# Smartwatch.net
KiCad netlist of a schematic drawn in Altium Designer
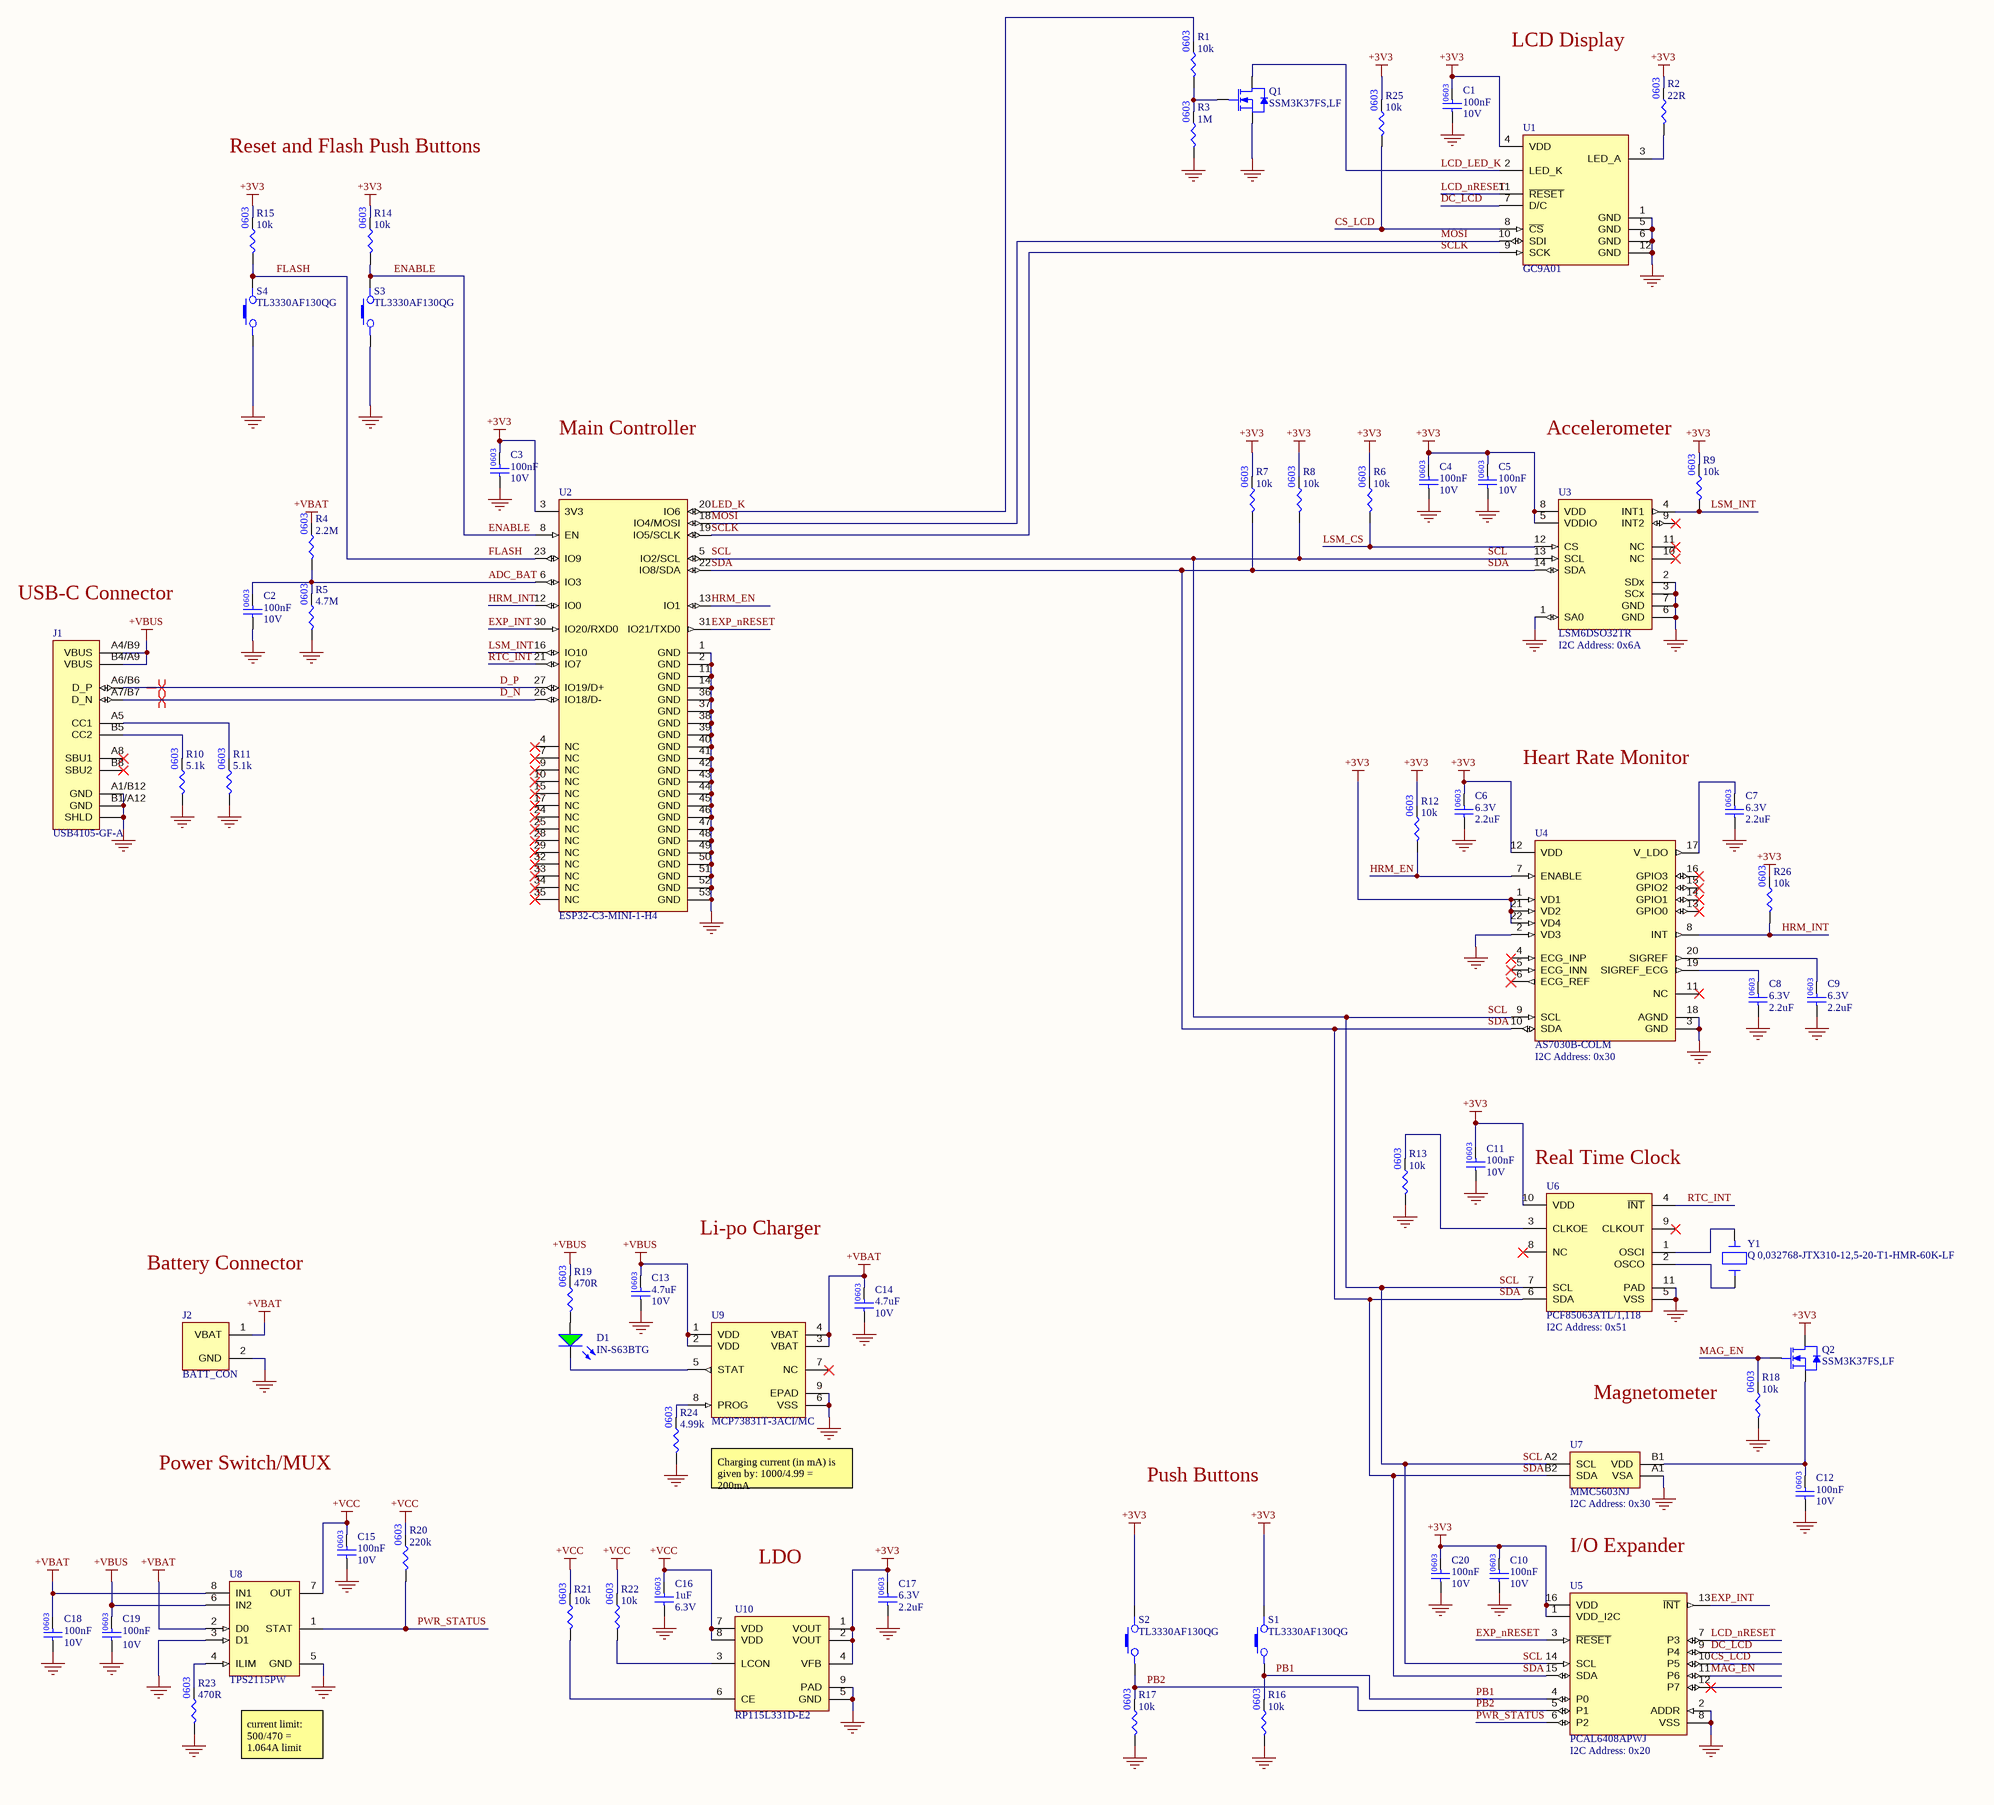
[diagram p0: Smartwatch.SchDoc]

(export (version "E")
  (design (tool "Eeschema 10.0.6"))
  (components
    (comp (ref "C1")
      (value "CC0603KRX7R6BB104")
      (footprint "CAP_0603")
      (description "CAP CER 0.1UF 10V X7R 0603")
      (fields
        (field (name "MANUFACTURER") "Yageo")
        (field (name "TOLERANCE") "10%")
        (field (name "CAPACITANCE") "100nF")
        (field (name "VOLTAGE RATING") "10V")
      )
      (libsource (lib "Smartwatch_Lib") (part "CC0603KRX7R6BB104"))
    )
    (comp (ref "C2")
      (value "CC0603KRX7R6BB104")
      (footprint "CAP_0603")
      (description "CAP CER 0.1UF 10V X7R 0603")
      (fields
        (field (name "MANUFACTURER") "Yageo")
        (field (name "TOLERANCE") "10%")
        (field (name "CAPACITANCE") "100nF")
        (field (name "VOLTAGE RATING") "10V")
      )
      (libsource (lib "Smartwatch_Lib") (part "CC0603KRX7R6BB104"))
    )
    (comp (ref "C3")
      (value "CC0603KRX7R6BB104")
      (footprint "CAP_0603")
      (description "CAP CER 0.1UF 10V X7R 0603")
      (fields
        (field (name "MANUFACTURER") "Yageo")
        (field (name "TOLERANCE") "10%")
        (field (name "CAPACITANCE") "100nF")
        (field (name "VOLTAGE RATING") "10V")
      )
      (libsource (lib "Smartwatch_Lib") (part "CC0603KRX7R6BB104"))
    )
    (comp (ref "C4")
      (value "CC0603KRX7R6BB104")
      (footprint "CAP_0603")
      (description "CAP CER 0.1UF 10V X7R 0603")
      (fields
        (field (name "MANUFACTURER") "Yageo")
        (field (name "TOLERANCE") "10%")
        (field (name "CAPACITANCE") "100nF")
        (field (name "VOLTAGE RATING") "10V")
      )
      (libsource (lib "Smartwatch_Lib") (part "CC0603KRX7R6BB104"))
    )
    (comp (ref "C5")
      (value "CC0603KRX7R6BB104")
      (footprint "CAP_0603")
      (description "CAP CER 0.1UF 10V X7R 0603")
      (fields
        (field (name "MANUFACTURER") "Yageo")
        (field (name "TOLERANCE") "10%")
        (field (name "CAPACITANCE") "100nF")
        (field (name "VOLTAGE RATING") "10V")
      )
      (libsource (lib "Smartwatch_Lib") (part "CC0603KRX7R6BB104"))
    )
    (comp (ref "C6")
      (value "CL10A225KQ8NNNC")
      (footprint "CAP_0603")
      (description "CAP CER 2.2UF 6.3V X5R 0603")
      (fields
        (field (name "MANUFACTURER") "Samsung")
        (field (name "TOLERANCE") "10%")
        (field (name "VOLTAGE RATING") "6.3V")
        (field (name "CAPACITANCE") "2.2uF")
      )
      (libsource (lib "Smartwatch_Lib") (part "CL10A225KQ8NNNC"))
    )
    (comp (ref "C7")
      (value "CL10A225KQ8NNNC")
      (footprint "CAP_0603")
      (description "CAP CER 2.2UF 6.3V X5R 0603")
      (fields
        (field (name "MANUFACTURER") "Samsung")
        (field (name "TOLERANCE") "10%")
        (field (name "VOLTAGE RATING") "6.3V")
        (field (name "CAPACITANCE") "2.2uF")
      )
      (libsource (lib "Smartwatch_Lib") (part "CL10A225KQ8NNNC"))
    )
    (comp (ref "C8")
      (value "CL10A225KQ8NNNC")
      (footprint "CAP_0603")
      (description "CAP CER 2.2UF 6.3V X5R 0603")
      (fields
        (field (name "MANUFACTURER") "Samsung")
        (field (name "TOLERANCE") "10%")
        (field (name "VOLTAGE RATING") "6.3V")
        (field (name "CAPACITANCE") "2.2uF")
      )
      (libsource (lib "Smartwatch_Lib") (part "CL10A225KQ8NNNC"))
    )
    (comp (ref "C9")
      (value "CL10A225KQ8NNNC")
      (footprint "CAP_0603")
      (description "CAP CER 2.2UF 6.3V X5R 0603")
      (fields
        (field (name "MANUFACTURER") "Samsung")
        (field (name "TOLERANCE") "10%")
        (field (name "VOLTAGE RATING") "6.3V")
        (field (name "CAPACITANCE") "2.2uF")
      )
      (libsource (lib "Smartwatch_Lib") (part "CL10A225KQ8NNNC"))
    )
    (comp (ref "C10")
      (value "CC0603KRX7R6BB104")
      (footprint "CAP_0603")
      (description "CAP CER 0.1UF 10V X7R 0603")
      (fields
        (field (name "MANUFACTURER") "Yageo")
        (field (name "TOLERANCE") "10%")
        (field (name "CAPACITANCE") "100nF")
        (field (name "VOLTAGE RATING") "10V")
      )
      (libsource (lib "Smartwatch_Lib") (part "CC0603KRX7R6BB104"))
    )
    (comp (ref "C11")
      (value "CC0603KRX7R6BB104")
      (footprint "CAP_0603")
      (description "CAP CER 0.1UF 10V X7R 0603")
      (fields
        (field (name "MANUFACTURER") "Yageo")
        (field (name "TOLERANCE") "10%")
        (field (name "CAPACITANCE") "100nF")
        (field (name "VOLTAGE RATING") "10V")
      )
      (libsource (lib "Smartwatch_Lib") (part "CC0603KRX7R6BB104"))
    )
    (comp (ref "C12")
      (value "CC0603KRX7R6BB104")
      (footprint "CAP_0603")
      (description "CAP CER 0.1UF 10V X7R 0603")
      (fields
        (field (name "MANUFACTURER") "Yageo")
        (field (name "TOLERANCE") "10%")
        (field (name "CAPACITANCE") "100nF")
        (field (name "VOLTAGE RATING") "10V")
      )
      (libsource (lib "Smartwatch_Lib") (part "CC0603KRX7R6BB104"))
    )
    (comp (ref "C13")
      (value "CL10A475KP8NNNC")
      (footprint "CAP_0603")
      (description "CAP CER 4.7UF 10V X5R 0603")
      (fields
        (field (name "MANUFACTURER") "Samsung")
        (field (name "TOLERANCE") "10%")
        (field (name "CAPACITANCE") "4.7uF")
        (field (name "VOLTAGE RATING") "10V")
      )
      (libsource (lib "Smartwatch_Lib") (part "CL10A475KP8NNNC"))
    )
    (comp (ref "C14")
      (value "CL10A475KP8NNNC")
      (footprint "CAP_0603")
      (description "CAP CER 4.7UF 10V X5R 0603")
      (fields
        (field (name "MANUFACTURER") "Samsung")
        (field (name "TOLERANCE") "10%")
        (field (name "CAPACITANCE") "4.7uF")
        (field (name "VOLTAGE RATING") "10V")
      )
      (libsource (lib "Smartwatch_Lib") (part "CL10A475KP8NNNC"))
    )
    (comp (ref "C15")
      (value "CC0603KRX7R6BB104")
      (footprint "CAP_0603")
      (description "CAP CER 0.1UF 10V X7R 0603")
      (fields
        (field (name "MANUFACTURER") "Yageo")
        (field (name "TOLERANCE") "10%")
        (field (name "CAPACITANCE") "100nF")
        (field (name "VOLTAGE RATING") "10V")
      )
      (libsource (lib "Smartwatch_Lib") (part "CC0603KRX7R6BB104"))
    )
    (comp (ref "C16")
      (value "CL10A105KQ8NNNC")
      (footprint "CAP_0603")
      (description "CAP CER 1UF 6.3V X5R 0603")
      (fields
        (field (name "MANUFACTURER") "Samsung")
        (field (name "TOLERANCE") "10%")
        (field (name "CAPACITANCE") "1uF")
        (field (name "VOLTAGE RATING (DC)") "6.3V")
      )
      (libsource (lib "Smartwatch_Lib") (part "CL10A105KQ8NNNC"))
    )
    (comp (ref "C17")
      (value "CL10A225KQ8NNNC")
      (footprint "CAP_0603")
      (description "CAP CER 2.2UF 6.3V X5R 0603")
      (fields
        (field (name "MANUFACTURER") "Samsung")
        (field (name "TOLERANCE") "10%")
        (field (name "VOLTAGE RATING") "6.3V")
        (field (name "CAPACITANCE") "2.2uF")
      )
      (libsource (lib "Smartwatch_Lib") (part "CL10A225KQ8NNNC"))
    )
    (comp (ref "C18")
      (value "CC0603KRX7R6BB104")
      (footprint "CAP_0603")
      (description "CAP CER 0.1UF 10V X7R 0603")
      (fields
        (field (name "MANUFACTURER") "Yageo")
        (field (name "TOLERANCE") "10%")
        (field (name "CAPACITANCE") "100nF")
        (field (name "VOLTAGE RATING") "10V")
      )
      (libsource (lib "Smartwatch_Lib") (part "CC0603KRX7R6BB104"))
    )
    (comp (ref "C19")
      (value "CC0603KRX7R6BB104")
      (footprint "CAP_0603")
      (description "CAP CER 0.1UF 10V X7R 0603")
      (fields
        (field (name "MANUFACTURER") "Yageo")
        (field (name "TOLERANCE") "10%")
        (field (name "CAPACITANCE") "100nF")
        (field (name "VOLTAGE RATING") "10V")
      )
      (libsource (lib "Smartwatch_Lib") (part "CC0603KRX7R6BB104"))
    )
    (comp (ref "C20")
      (value "CC0603KRX7R6BB104")
      (footprint "CAP_0603")
      (description "CAP CER 0.1UF 10V X7R 0603")
      (fields
        (field (name "MANUFACTURER") "Yageo")
        (field (name "TOLERANCE") "10%")
        (field (name "CAPACITANCE") "100nF")
        (field (name "VOLTAGE RATING") "10V")
      )
      (libsource (lib "Smartwatch_Lib") (part "CC0603KRX7R6BB104"))
    )
    (comp (ref "D1")
      (value "IN-S63BTG")
      (footprint "LED_0603")
      (description "LED Uni-Color Green 530nm 2-Pin Chip 0603(1608Metric) T/R")
      (fields (field (name "MANUFACTURER") "Inolux"))
      (libsource (lib "Smartwatch_Lib") (part "IN-S63BTG"))
    )
    (comp (ref "J1")
      (value "USB4105-GF-A")
      (footprint "USB4105-GF-A")
      (description "Conn USB 2.0 Type C RCP 24 POS 0.3mm/0.5mm Solder RA SMD 24 Terminal 1 Port T/R")
      (fields (field (name "MANUFACTURER") "Global Connector Technology"))
      (libsource (lib "Smartwatch_Lib") (part "USB4105-GF-A"))
    )
    (comp (ref "J2")
      (value "BATT_CON")
      (footprint "BATT_CON")
      (description "Pads for Battery Connection")
      (libsource (lib "Smartwatch_Lib") (part "BATT_CON"))
    )
    (comp (ref "Q1")
      (value "SSM3K37FS,LF")
      (footprint "SSM3K37FS,LF")
      (description "MOSFET NCH 20V 200MA SSM")
      (fields
        (field (name "MANUFACTURER") "Toshiba")
        (field (name "MANUFACTURER PART NUMBER") "SSM3K37FS,LF")
      )
      (libsource (lib "Smartwatch_Lib") (part "SSM3K37FS,LF"))
    )
    (comp (ref "Q2")
      (value "SSM3K37FS,LF")
      (footprint "SSM3K37FS,LF")
      (description "MOSFET NCH 20V 200MA SSM")
      (fields
        (field (name "MANUFACTURER") "Toshiba")
        (field (name "MANUFACTURER PART NUMBER") "SSM3K37FS,LF")
      )
      (libsource (lib "Smartwatch_Lib") (part "SSM3K37FS,LF"))
    )
    (comp (ref "R1")
      (value "RNCP0603FTD10K0")
      (footprint "RES_0603")
      (description "Res Thin Film 0603 10K Ohm 1% 1/8W ±100ppm/°C Molded SMD SMD Paper T/R")
      (fields
        (field (name "MANUFACTURER") "Stackpole Electronics")
        (field (name "TOLERANCE") "1%")
        (field (name "RESISTANCE") "10k")
      )
      (libsource (lib "Smartwatch_Lib") (part "RNCP0603FTD10K0"))
    )
    (comp (ref "R2")
      (value "RC0603FR-0722RL")
      (footprint "RES_0603")
      (description "RES 22 OHM 1% 1/10W 0603")
      (fields
        (field (name "MANUFACTURER") "Yageo")
        (field (name "TOLERANCE") "1%")
        (field (name "RESISTANCE") "22R")
      )
      (libsource (lib "Smartwatch_Lib") (part "RC0603FR-0722RL"))
    )
    (comp (ref "R3")
      (value "RC0603FR-071ML")
      (footprint "RES_0603")
      (description "RES 1M OHM 1% 1/10W 0603")
      (fields
        (field (name "MANUFACTURER") "Yageo")
        (field (name "TOLERANCE") "1%")
        (field (name "RESISTANCE") "1M")
      )
      (libsource (lib "Smartwatch_Lib") (part "RC0603FR-071ML"))
    )
    (comp (ref "R4")
      (value "RC0603FR-072M2L")
      (footprint "RES_0603")
      (description "RES SMD 2.2M OHM 1% 1/10W 0603")
      (fields
        (field (name "MANUFACTURER") "Yageo")
        (field (name "TOLERANCE") "1%")
        (field (name "RESISTANCE") "2.2M")
      )
      (libsource (lib "Smartwatch_Lib") (part "RC0603FR-072M2L"))
    )
    (comp (ref "R5")
      (value "RC0603FR-074M7L")
      (footprint "RES_0603")
      (description "RES 4.7M OHM 1% 1/10W 0603")
      (fields
        (field (name "MANUFACTURER") "Yageo")
        (field (name "TOLERANCE") "1%")
        (field (name "RESISTANCE") "4.7M")
      )
      (libsource (lib "Smartwatch_Lib") (part "RC0603FR-074M7L"))
    )
    (comp (ref "R6")
      (value "RNCP0603FTD10K0")
      (footprint "RES_0603")
      (description "Res Thin Film 0603 10K Ohm 1% 1/8W ±100ppm/°C Molded SMD SMD Paper T/R")
      (fields
        (field (name "MANUFACTURER") "Stackpole Electronics")
        (field (name "TOLERANCE") "1%")
        (field (name "RESISTANCE") "10k")
      )
      (libsource (lib "Smartwatch_Lib") (part "RNCP0603FTD10K0"))
    )
    (comp (ref "R7")
      (value "RNCP0603FTD10K0")
      (footprint "RES_0603")
      (description "Res Thin Film 0603 10K Ohm 1% 1/8W ±100ppm/°C Molded SMD SMD Paper T/R")
      (fields
        (field (name "MANUFACTURER") "Stackpole Electronics")
        (field (name "TOLERANCE") "1%")
        (field (name "RESISTANCE") "10k")
      )
      (libsource (lib "Smartwatch_Lib") (part "RNCP0603FTD10K0"))
    )
    (comp (ref "R8")
      (value "RNCP0603FTD10K0")
      (footprint "RES_0603")
      (description "Res Thin Film 0603 10K Ohm 1% 1/8W ±100ppm/°C Molded SMD SMD Paper T/R")
      (fields
        (field (name "MANUFACTURER") "Stackpole Electronics")
        (field (name "TOLERANCE") "1%")
        (field (name "RESISTANCE") "10k")
      )
      (libsource (lib "Smartwatch_Lib") (part "RNCP0603FTD10K0"))
    )
    (comp (ref "R9")
      (value "RNCP0603FTD10K0")
      (footprint "RES_0603")
      (description "Res Thin Film 0603 10K Ohm 1% 1/8W ±100ppm/°C Molded SMD SMD Paper T/R")
      (fields
        (field (name "MANUFACTURER") "Stackpole Electronics")
        (field (name "TOLERANCE") "1%")
        (field (name "RESISTANCE") "10k")
      )
      (libsource (lib "Smartwatch_Lib") (part "RNCP0603FTD10K0"))
    )
    (comp (ref "R10")
      (value "RMCF0603FT5K10")
      (footprint "RES_0603")
      (description "Res Thick Film 0603 5.1K Ohm 1% 0.1W(1/10W) ±100ppm/C Pad SMD Automotive T/R")
      (fields
        (field (name "MANUFACTURER") "Stackpole Electronics")
        (field (name "TOLERANCE") "1%")
        (field (name "RESISTANCE") "5.1k")
      )
      (libsource (lib "Smartwatch_Lib") (part "RMCF0603FT5K10"))
    )
    (comp (ref "R11")
      (value "RMCF0603FT5K10")
      (footprint "RES_0603")
      (description "Res Thick Film 0603 5.1K Ohm 1% 0.1W(1/10W) ±100ppm/C Pad SMD Automotive T/R")
      (fields
        (field (name "MANUFACTURER") "Stackpole Electronics")
        (field (name "TOLERANCE") "1%")
        (field (name "RESISTANCE") "5.1k")
      )
      (libsource (lib "Smartwatch_Lib") (part "RMCF0603FT5K10"))
    )
    (comp (ref "R12")
      (value "RNCP0603FTD10K0")
      (footprint "RES_0603")
      (description "Res Thin Film 0603 10K Ohm 1% 1/8W ±100ppm/°C Molded SMD SMD Paper T/R")
      (fields
        (field (name "MANUFACTURER") "Stackpole Electronics")
        (field (name "TOLERANCE") "1%")
        (field (name "RESISTANCE") "10k")
      )
      (libsource (lib "Smartwatch_Lib") (part "RNCP0603FTD10K0"))
    )
    (comp (ref "R13")
      (value "RNCP0603FTD10K0")
      (footprint "RES_0603")
      (description "Res Thin Film 0603 10K Ohm 1% 1/8W ±100ppm/°C Molded SMD SMD Paper T/R")
      (fields
        (field (name "MANUFACTURER") "Stackpole Electronics")
        (field (name "TOLERANCE") "1%")
        (field (name "RESISTANCE") "10k")
      )
      (libsource (lib "Smartwatch_Lib") (part "RNCP0603FTD10K0"))
    )
    (comp (ref "R14")
      (value "RNCP0603FTD10K0")
      (footprint "RES_0603")
      (description "Res Thin Film 0603 10K Ohm 1% 1/8W ±100ppm/°C Molded SMD SMD Paper T/R")
      (fields
        (field (name "MANUFACTURER") "Stackpole Electronics")
        (field (name "TOLERANCE") "1%")
        (field (name "RESISTANCE") "10k")
      )
      (libsource (lib "Smartwatch_Lib") (part "RNCP0603FTD10K0"))
    )
    (comp (ref "R15")
      (value "RNCP0603FTD10K0")
      (footprint "RES_0603")
      (description "Res Thin Film 0603 10K Ohm 1% 1/8W ±100ppm/°C Molded SMD SMD Paper T/R")
      (fields
        (field (name "MANUFACTURER") "Stackpole Electronics")
        (field (name "TOLERANCE") "1%")
        (field (name "RESISTANCE") "10k")
      )
      (libsource (lib "Smartwatch_Lib") (part "RNCP0603FTD10K0"))
    )
    (comp (ref "R16")
      (value "RNCP0603FTD10K0")
      (footprint "RES_0603")
      (description "Res Thin Film 0603 10K Ohm 1% 1/8W ±100ppm/°C Molded SMD SMD Paper T/R")
      (fields
        (field (name "MANUFACTURER") "Stackpole Electronics")
        (field (name "TOLERANCE") "1%")
        (field (name "RESISTANCE") "10k")
      )
      (libsource (lib "Smartwatch_Lib") (part "RNCP0603FTD10K0"))
    )
    (comp (ref "R17")
      (value "RNCP0603FTD10K0")
      (footprint "RES_0603")
      (description "Res Thin Film 0603 10K Ohm 1% 1/8W ±100ppm/°C Molded SMD SMD Paper T/R")
      (fields
        (field (name "MANUFACTURER") "Stackpole Electronics")
        (field (name "TOLERANCE") "1%")
        (field (name "RESISTANCE") "10k")
      )
      (libsource (lib "Smartwatch_Lib") (part "RNCP0603FTD10K0"))
    )
    (comp (ref "R18")
      (value "RNCP0603FTD10K0")
      (footprint "RES_0603")
      (description "Res Thin Film 0603 10K Ohm 1% 1/8W ±100ppm/°C Molded SMD SMD Paper T/R")
      (fields
        (field (name "MANUFACTURER") "Stackpole Electronics")
        (field (name "TOLERANCE") "1%")
        (field (name "RESISTANCE") "10k")
      )
      (libsource (lib "Smartwatch_Lib") (part "RNCP0603FTD10K0"))
    )
    (comp (ref "R19")
      (value "RC0603FR-07470RL")
      (footprint "RES_0603")
      (description "RES 470 OHM 1% 1/10W 0603")
      (fields
        (field (name "MANUFACTURER") "Yageo")
        (field (name "TOLERANCE") "1%")
        (field (name "RESISTANCE") "470R")
      )
      (libsource (lib "Smartwatch_Lib") (part "RC0603FR-07470RL"))
    )
    (comp (ref "R20")
      (value "RMCF0603FT220K")
      (footprint "RES_0603")
      (description "Res Thick Film 0603 220K Ohm 1% 0.1W(1/10W) ±100ppm/C Pad SMD Automotive T/R")
      (fields
        (field (name "MANUFACTURER") "Stackpole Electronics")
        (field (name "TOLERANCE") "1%")
        (field (name "RESISTANCE") "220k")
      )
      (libsource (lib "Smartwatch_Lib") (part "RMCF0603FT220K"))
    )
    (comp (ref "R21")
      (value "RNCP0603FTD10K0")
      (footprint "RES_0603")
      (description "Res Thin Film 0603 10K Ohm 1% 1/8W ±100ppm/°C Molded SMD SMD Paper T/R")
      (fields
        (field (name "MANUFACTURER") "Stackpole Electronics")
        (field (name "TOLERANCE") "1%")
        (field (name "RESISTANCE") "10k")
      )
      (libsource (lib "Smartwatch_Lib") (part "RNCP0603FTD10K0"))
    )
    (comp (ref "R22")
      (value "RNCP0603FTD10K0")
      (footprint "RES_0603")
      (description "Res Thin Film 0603 10K Ohm 1% 1/8W ±100ppm/°C Molded SMD SMD Paper T/R")
      (fields
        (field (name "MANUFACTURER") "Stackpole Electronics")
        (field (name "TOLERANCE") "1%")
        (field (name "RESISTANCE") "10k")
      )
      (libsource (lib "Smartwatch_Lib") (part "RNCP0603FTD10K0"))
    )
    (comp (ref "R23")
      (value "RC0603FR-07470RL")
      (footprint "RES_0603")
      (description "RES 470 OHM 1% 1/10W 0603")
      (fields
        (field (name "MANUFACTURER") "Yageo")
        (field (name "TOLERANCE") "1%")
        (field (name "RESISTANCE") "470R")
      )
      (libsource (lib "Smartwatch_Lib") (part "RC0603FR-07470RL"))
    )
    (comp (ref "R24")
      (value "RC0603FR-074K99L")
      (footprint "RES_0603")
      (description "RES 4.99K OHM 1% 1/10W 0603")
      (fields
        (field (name "MANUFACTURER") "Yageo")
        (field (name "TOLERANCE") "1%")
        (field (name "RESISTANCE") "4.99k")
      )
      (libsource (lib "Smartwatch_Lib") (part "RC0603FR-074K99L"))
    )
    (comp (ref "R25")
      (value "RNCP0603FTD10K0")
      (footprint "RES_0603")
      (description "Res Thin Film 0603 10K Ohm 1% 1/8W ±100ppm/°C Molded SMD SMD Paper T/R")
      (fields
        (field (name "MANUFACTURER") "Stackpole Electronics")
        (field (name "TOLERANCE") "1%")
        (field (name "RESISTANCE") "10k")
      )
      (libsource (lib "Smartwatch_Lib") (part "RNCP0603FTD10K0"))
    )
    (comp (ref "R26")
      (value "RNCP0603FTD10K0")
      (footprint "RES_0603")
      (description "Res Thin Film 0603 10K Ohm 1% 1/8W ±100ppm/°C Molded SMD SMD Paper T/R")
      (fields
        (field (name "MANUFACTURER") "Stackpole Electronics")
        (field (name "TOLERANCE") "1%")
        (field (name "RESISTANCE") "10k")
      )
      (libsource (lib "Smartwatch_Lib") (part "RNCP0603FTD10K0"))
    )
    (comp (ref "S1")
      (value "TL3330AF130QG")
      (footprint "TL3330AF130QG")
      (description "Switch Tactile N.O. SPST Rectangular Button Gull Wing 0.05A 12VDC 50000Cycles 1.27N SMD T/R")
      (fields
        (field (name "MANUFACTURER") "E-Switch")
        (field (name "MANUFACTURER PART NUMBER") "TL3330AF130QG")
      )
      (libsource (lib "Smartwatch_Lib") (part "TL3330AF130QG"))
    )
    (comp (ref "S2")
      (value "TL3330AF130QG")
      (footprint "TL3330AF130QG")
      (description "Switch Tactile N.O. SPST Rectangular Button Gull Wing 0.05A 12VDC 50000Cycles 1.27N SMD T/R")
      (fields
        (field (name "MANUFACTURER") "E-Switch")
        (field (name "MANUFACTURER PART NUMBER") "TL3330AF130QG")
      )
      (libsource (lib "Smartwatch_Lib") (part "TL3330AF130QG"))
    )
    (comp (ref "S3")
      (value "TL3330AF130QG")
      (footprint "TL3330AF130QG")
      (description "Switch Tactile N.O. SPST Rectangular Button Gull Wing 0.05A 12VDC 50000Cycles 1.27N SMD T/R")
      (fields
        (field (name "MANUFACTURER") "E-Switch")
        (field (name "MANUFACTURER PART NUMBER") "TL3330AF130QG")
      )
      (libsource (lib "Smartwatch_Lib") (part "TL3330AF130QG"))
    )
    (comp (ref "S4")
      (value "TL3330AF130QG")
      (footprint "TL3330AF130QG")
      (description "Switch Tactile N.O. SPST Rectangular Button Gull Wing 0.05A 12VDC 50000Cycles 1.27N SMD T/R")
      (fields
        (field (name "MANUFACTURER") "E-Switch")
        (field (name "MANUFACTURER PART NUMBER") "TL3330AF130QG")
      )
      (libsource (lib "Smartwatch_Lib") (part "TL3330AF130QG"))
    )
    (comp (ref "U1")
      (value "GC9A01")
      (footprint "GC9A01")
      (description "GC9A01 LCD Display")
      (libsource (lib "Smartwatch_Lib") (part "GC9A01"))
    )
    (comp (ref "U2")
      (value "ESP32-C3-MINI-1-H4")
      (footprint "ESP32-C3-MINI-1-H4")
      (description "SMD Module, ESP32-C3FH4, Pcb Ant")
      (fields (field (name "MANUFACTURER") "Espressif Systems"))
      (libsource (lib "Smartwatch_Lib") (part "ESP32-C3-MINI-1-H4"))
    )
    (comp (ref "U3")
      (value "LSM6DSO32TR")
      (footprint "LSM6DSO32")
      (description "Accelerometer and 3D Gyroscope 3D Always-On 1.71V to 3.6V 0.55mA 14-Pin LGA T/R")
      (fields (field (name "MANUFACTURER") "STMicroelectronics"))
      (libsource (lib "Smartwatch_Lib") (part "LSM6DSO32TR"))
    )
    (comp (ref "U4")
      (value "AS7030B-COLM")
      (footprint "AS7030B-COLM")
      (description "AS703x Series 5.5 V Medical or Consumer Grade Vital Sign Sensor Module - OLGA-22")
      (fields (field (name "MANUFACTURER") "ams"))
      (libsource (lib "Smartwatch_Lib") (part "AS7030B-COLM"))
    )
    (comp (ref "U5")
      (value "PCAL6408APWJ")
      (footprint "PCAL6408APWJ")
      (description "NXP - PCAL6408APWJ - I/O-Erweiterung, 8bit, 400 kHz, I2C, 1.65 V, 5.5 V, TSSOP")
      (fields
        (field (name "MANUFACTURER") "NXP Semiconductors")
        (field (name "MANUFACTURER PART NUMBER") "PCAL6408APWJ")
      )
      (libsource (lib "Smartwatch_Lib") (part "PCAL6408APWJ"))
    )
    (comp (ref "U6")
      (value "PCF85063ATL/1,118")
      (footprint "PCF85063ATL/1,118")
      (description "IC RTC CLK/CALENDAR I2C 10-SON")
      (fields (field (name "MANUFACTURER") "NXP Semiconductors"))
      (libsource (lib "Smartwatch_Lib") (part "PCF85063ATL/1,118"))
    )
    (comp (ref "U7")
      (value "MMC5603NJ")
      (footprint "MMC5603NJ")
      (description "3-AXIS Amr Magnetic Sensor")
      (fields (field (name "MANUFACTURER") "Memsic") (field (name "MANUFACTURER PART NUMBER") "MMC5603NJ"))
      (libsource (lib "Smartwatch_Lib") (part "MMC5603NJ"))
    )
    (comp (ref "U8")
      (value "TPS2115PW")
      (footprint "TPS2115PW")
      (description "Pwr Mux Autoswitch 1.5V to 5.5V 1.25A 8-Pin TSSOP Tube")
      (fields (field (name "MANUFACTURER") "Texas Instruments"))
      (libsource (lib "Smartwatch_Lib") (part "TPS2115PW"))
    )
    (comp (ref "U9")
      (value "MCP73831T-3ACI/MC")
      (footprint "MCP73831T-3ACI/MC")
      (description "Battery Management - Advanced Lithium-Ion/-Polymer Charge mgnt contr")
      (fields (field (name "MANUFACTURER") "Microchip"))
      (libsource (lib "Smartwatch_Lib") (part "MCP73831T-3ACI/MC"))
    )
    (comp (ref "U10")
      (value "RP115L331D-E2")
      (footprint "RP115L331D-E2")
      (description "LDO Regulator Pos 3.3V 0.5A/1A 8-Pin DFN EP T/R")
      (fields (field (name "MANUFACTURER") "Ricoh"))
      (libsource (lib "Smartwatch_Lib") (part "RP115L331D-E2"))
    )
    (comp (ref "Y1")
      (value "Q 0,032768-JTX310-12,5-20-T1-HMR-60K-LF")
      (footprint "Q 0,032768-JTX310-12,5-20-T1-HMR-60K-LF")
      (description "Crystal 32.7680KHZ 12.5PF SMD")
      (fields
        (field (name "MANUFACTURER") "Jauch")
        (field (name "MANUFACTURER PART NUMBER") "Q 0,032768-JTX310-12,5-20-T1-HMR-60K-LF")
      )
      (libsource (lib "Smartwatch_Lib") (part "Q 0,032768-JTX310-12,5-20-T1-HMR-60K-LF"))
    )
  )
  (nets
    (net (code "1") (name "+3V3") (class "Default")
      (node (ref "C1") (pin "2") (pinfunction "2_2") (pintype "passive"))
      (node (ref "C10") (pin "2") (pinfunction "2_2") (pintype "passive"))
      (node (ref "C11") (pin "2") (pinfunction "2_2") (pintype "passive"))
      (node (ref "C17") (pin "2") (pinfunction "2_2") (pintype "passive"))
      (node (ref "C20") (pin "2") (pinfunction "2_2") (pintype "passive"))
      (node (ref "C3") (pin "2") (pinfunction "2_2") (pintype "passive"))
      (node (ref "C4") (pin "2") (pinfunction "2_2") (pintype "passive"))
      (node (ref "C5") (pin "2") (pinfunction "2_2") (pintype "passive"))
      (node (ref "C6") (pin "2") (pinfunction "2_2") (pintype "passive"))
      (node (ref "Q2") (pin "1") (pinfunction "Drain_1") (pintype "passive"))
      (node (ref "R12") (pin "2") (pinfunction "2_2") (pintype "passive"))
      (node (ref "R14") (pin "2") (pinfunction "2_2") (pintype "passive"))
      (node (ref "R15") (pin "2") (pinfunction "2_2") (pintype "passive"))
      (node (ref "R2") (pin "2") (pinfunction "2_2") (pintype "passive"))
      (node (ref "R25") (pin "2") (pinfunction "2_2") (pintype "passive"))
      (node (ref "R26") (pin "2") (pinfunction "2_2") (pintype "passive"))
      (node (ref "R6") (pin "2") (pinfunction "2_2") (pintype "passive"))
      (node (ref "R7") (pin "2") (pinfunction "2_2") (pintype "passive"))
      (node (ref "R8") (pin "2") (pinfunction "2_2") (pintype "passive"))
      (node (ref "R9") (pin "2") (pinfunction "2_2") (pintype "passive"))
      (node (ref "S1") (pin "1") (pintype "passive"))
      (node (ref "S2") (pin "1") (pintype "passive"))
      (node (ref "U1") (pin "4") (pinfunction "VDD_4") (pintype "passive"))
      (node (ref "U10") (pin "1") (pinfunction "VOUT_1") (pintype "passive"))
      (node (ref "U10") (pin "2") (pinfunction "VOUT_2") (pintype "passive"))
      (node (ref "U10") (pin "4") (pinfunction "VFB_4") (pintype "passive"))
      (node (ref "U2") (pin "3") (pinfunction "3V3_3") (pintype "power_in"))
      (node (ref "U3") (pin "5") (pinfunction "VDDIO_5") (pintype "power_in"))
      (node (ref "U3") (pin "8") (pinfunction "VDD_8") (pintype "power_in"))
      (node (ref "U4") (pin "1") (pinfunction "VD1_1") (pintype "input"))
      (node (ref "U4") (pin "12") (pinfunction "VDD_12") (pintype "power_in"))
      (node (ref "U4") (pin "21") (pinfunction "VD2_21") (pintype "input"))
      (node (ref "U4") (pin "22") (pinfunction "VD4_22") (pintype "input"))
      (node (ref "U5") (pin "1") (pinfunction "VDD_I2C_1") (pintype "power_in"))
      (node (ref "U5") (pin "16") (pinfunction "VDD_16") (pintype "power_in"))
      (node (ref "U6") (pin "10") (pinfunction "VDD_10") (pintype "passive"))
    )
    (net (code "2") (name "+VBAT") (class "Default")
      (node (ref "C14") (pin "2") (pinfunction "2_2") (pintype "passive"))
      (node (ref "C18") (pin "2") (pinfunction "2_2") (pintype "passive"))
      (node (ref "J2") (pin "1") (pinfunction "VBAT_1") (pintype "passive"))
      (node (ref "R4") (pin "2") (pinfunction "2_2") (pintype "passive"))
      (node (ref "U8") (pin "2") (pinfunction "D0_2") (pintype "input"))
      (node (ref "U8") (pin "8") (pinfunction "IN1_8") (pintype "power_in"))
      (node (ref "U9") (pin "3") (pinfunction "VBAT_3") (pintype "passive"))
      (node (ref "U9") (pin "4") (pinfunction "VBAT_4") (pintype "passive"))
    )
    (net (code "3") (name "+VBUS") (class "Default")
      (node (ref "C13") (pin "2") (pinfunction "2_2") (pintype "passive"))
      (node (ref "C19") (pin "2") (pinfunction "2_2") (pintype "passive"))
      (node (ref "J1") (pin "A4/B9") (pinfunction "VBUS_A4/B9") (pintype "power_in"))
      (node (ref "J1") (pin "B4/A9") (pinfunction "VBUS_B4/A9") (pintype "power_in"))
      (node (ref "R19") (pin "2") (pinfunction "2_2") (pintype "passive"))
      (node (ref "U8") (pin "6") (pinfunction "IN2_6") (pintype "power_in"))
      (node (ref "U9") (pin "1") (pinfunction "VDD_1") (pintype "passive"))
      (node (ref "U9") (pin "2") (pinfunction "VDD_2") (pintype "passive"))
    )
    (net (code "4") (name "+VCC") (class "Default")
      (node (ref "C15") (pin "2") (pinfunction "2_2") (pintype "passive"))
      (node (ref "C16") (pin "2") (pinfunction "2_2") (pintype "passive"))
      (node (ref "R20") (pin "2") (pinfunction "2_2") (pintype "passive"))
      (node (ref "R21") (pin "2") (pinfunction "2_2") (pintype "passive"))
      (node (ref "R22") (pin "2") (pinfunction "2_2") (pintype "passive"))
      (node (ref "U10") (pin "7") (pinfunction "VDD_7") (pintype "passive"))
      (node (ref "U10") (pin "8") (pinfunction "VDD_8") (pintype "passive"))
      (node (ref "U8") (pin "7") (pinfunction "OUT_7") (pintype "power_in"))
    )
    (net (code "5") (name "/ADC_BAT") (class "Default")
      (node (ref "C2") (pin "2") (pinfunction "2_2") (pintype "passive"))
      (node (ref "R4") (pin "1") (pinfunction "1_1") (pintype "passive"))
      (node (ref "R5") (pin "2") (pinfunction "2_2") (pintype "passive"))
      (node (ref "U2") (pin "6") (pinfunction "IO3_6") (pintype "bidirectional"))
    )
    (net (code "6") (name "/CS_LCD") (class "Default")
      (node (ref "R25") (pin "1") (pinfunction "1_1") (pintype "passive"))
      (node (ref "U1") (pin "8") (pinfunction "~{CS}_8") (pintype "input"))
      (node (ref "U5") (pin "10") (pinfunction "P5_10") (pintype "bidirectional"))
    )
    (net (code "7") (name "/DC_LCD") (class "Default")
      (node (ref "U1") (pin "7") (pinfunction "D/C_7") (pintype "passive"))
      (node (ref "U5") (pin "9") (pinfunction "P4_9") (pintype "bidirectional"))
    )
    (net (code "8") (name "/D_N") (class "Default")
      (node (ref "J1") (pin "A7/B7") (pinfunction "D_N_A7/B7") (pintype "bidirectional"))
      (node (ref "U2") (pin "26") (pinfunction "IO18/D-_26") (pintype "bidirectional"))
    )
    (net (code "9") (name "/D_P") (class "Default")
      (node (ref "J1") (pin "A6/B6") (pinfunction "D_P_A6/B6") (pintype "bidirectional"))
      (node (ref "U2") (pin "27") (pinfunction "IO19/D+_27") (pintype "bidirectional"))
    )
    (net (code "10") (name "/ENABLE") (class "Default")
      (node (ref "R14") (pin "1") (pinfunction "1_1") (pintype "passive"))
      (node (ref "S3") (pin "1") (pintype "passive"))
      (node (ref "U2") (pin "8") (pinfunction "EN_8") (pintype "input"))
    )
    (net (code "11") (name "/EXP_INT") (class "Default")
      (node (ref "U2") (pin "30") (pinfunction "IO20/RXD0_30") (pintype "input"))
      (node (ref "U5") (pin "13") (pinfunction "~{INT}_13") (pintype "output"))
    )
    (net (code "12") (name "/EXP_nRESET") (class "Default")
      (node (ref "U2") (pin "31") (pinfunction "IO21/TXD0_31") (pintype "output"))
      (node (ref "U5") (pin "3") (pinfunction "~{RESET}_3") (pintype "input"))
    )
    (net (code "13") (name "/FLASH") (class "Default")
      (node (ref "R15") (pin "1") (pinfunction "1_1") (pintype "passive"))
      (node (ref "S4") (pin "1") (pintype "passive"))
      (node (ref "U2") (pin "23") (pinfunction "IO9_23") (pintype "bidirectional"))
    )
    (net (code "14") (name "/HRM_EN") (class "Default")
      (node (ref "R12") (pin "1") (pinfunction "1_1") (pintype "passive"))
      (node (ref "U2") (pin "13") (pinfunction "IO1_13") (pintype "bidirectional"))
      (node (ref "U4") (pin "7") (pinfunction "ENABLE_7") (pintype "input"))
    )
    (net (code "15") (name "/HRM_INT") (class "Default")
      (node (ref "R26") (pin "1") (pinfunction "1_1") (pintype "passive"))
      (node (ref "U2") (pin "12") (pinfunction "IO0_12") (pintype "bidirectional"))
      (node (ref "U4") (pin "8") (pinfunction "INT_8") (pintype "output"))
    )
    (net (code "16") (name "/LCD_LED_K") (class "Default")
      (node (ref "Q1") (pin "1") (pinfunction "Drain_1") (pintype "passive"))
      (node (ref "U1") (pin "2") (pinfunction "LED_K_2") (pintype "passive"))
    )
    (net (code "17") (name "/LCD_nRESET") (class "Default")
      (node (ref "U1") (pin "11") (pinfunction "~{RESET}_11") (pintype "passive"))
      (node (ref "U5") (pin "7") (pinfunction "P3_7") (pintype "bidirectional"))
    )
    (net (code "18") (name "/LED_K") (class "Default")
      (node (ref "R1") (pin "2") (pinfunction "2_2") (pintype "passive"))
      (node (ref "U2") (pin "20") (pinfunction "IO6_20") (pintype "bidirectional"))
    )
    (net (code "19") (name "/LSM_CS") (class "Default")
      (node (ref "R6") (pin "1") (pinfunction "1_1") (pintype "passive"))
      (node (ref "U3") (pin "12") (pinfunction "CS_12") (pintype "input"))
    )
    (net (code "20") (name "/LSM_INT") (class "Default")
      (node (ref "R9") (pin "1") (pinfunction "1_1") (pintype "passive"))
      (node (ref "U2") (pin "16") (pinfunction "IO10_16") (pintype "bidirectional"))
      (node (ref "U3") (pin "4") (pinfunction "INT1_4") (pintype "output"))
    )
    (net (code "21") (name "/MAG_EN") (class "Default")
      (node (ref "Q2") (pin "2") (pinfunction "Gate_2") (pintype "passive"))
      (node (ref "R18") (pin "2") (pinfunction "2_2") (pintype "passive"))
      (node (ref "U5") (pin "11") (pinfunction "P6_11") (pintype "bidirectional"))
    )
    (net (code "22") (name "/MOSI") (class "Default")
      (node (ref "U1") (pin "10") (pinfunction "SDI_10") (pintype "bidirectional"))
      (node (ref "U2") (pin "18") (pinfunction "IO4/MOSI_18") (pintype "bidirectional"))
    )
    (net (code "23") (name "/PB1") (class "Default")
      (node (ref "R16") (pin "2") (pinfunction "2_2") (pintype "passive"))
      (node (ref "S1") (pin "2") (pintype "passive"))
      (node (ref "U5") (pin "4") (pinfunction "P0_4") (pintype "bidirectional"))
    )
    (net (code "24") (name "/PB2") (class "Default")
      (node (ref "R17") (pin "2") (pinfunction "2_2") (pintype "passive"))
      (node (ref "S2") (pin "2") (pintype "passive"))
      (node (ref "U5") (pin "5") (pinfunction "P1_5") (pintype "bidirectional"))
    )
    (net (code "25") (name "/PWR_STATUS") (class "Default")
      (node (ref "R20") (pin "1") (pinfunction "1_1") (pintype "passive"))
      (node (ref "U5") (pin "6") (pinfunction "P2_6") (pintype "bidirectional"))
      (node (ref "U8") (pin "1") (pinfunction "STAT_1") (pintype "tri_state"))
    )
    (net (code "26") (name "/RTC_INT") (class "Default")
      (node (ref "U2") (pin "21") (pinfunction "IO7_21") (pintype "bidirectional"))
      (node (ref "U6") (pin "4") (pinfunction "~{INT}_4") (pintype "passive"))
    )
    (net (code "27") (name "/SCL") (class "Default")
      (node (ref "R8") (pin "1") (pinfunction "1_1") (pintype "passive"))
      (node (ref "U2") (pin "5") (pinfunction "IO2/SCL_5") (pintype "bidirectional"))
      (node (ref "U3") (pin "13") (pinfunction "SCL_13") (pintype "input"))
      (node (ref "U4") (pin "9") (pinfunction "SCL_9") (pintype "input"))
      (node (ref "U5") (pin "14") (pinfunction "SCL_14") (pintype "input"))
      (node (ref "U6") (pin "7") (pinfunction "SCL_7") (pintype "passive"))
      (node (ref "U7") (pin "A2") (pinfunction "SCL_A2") (pintype "passive"))
    )
    (net (code "28") (name "/SCLK") (class "Default")
      (node (ref "U1") (pin "9") (pinfunction "SCK_9") (pintype "input"))
      (node (ref "U2") (pin "19") (pinfunction "IO5/SCLK_19") (pintype "bidirectional"))
    )
    (net (code "29") (name "/SDA") (class "Default")
      (node (ref "R7") (pin "1") (pinfunction "1_1") (pintype "passive"))
      (node (ref "U2") (pin "22") (pinfunction "IO8/SDA_22") (pintype "bidirectional"))
      (node (ref "U3") (pin "14") (pinfunction "SDA_14") (pintype "bidirectional"))
      (node (ref "U4") (pin "10") (pinfunction "SDA_10") (pintype "bidirectional"))
      (node (ref "U5") (pin "15") (pinfunction "SDA_15") (pintype "bidirectional"))
      (node (ref "U6") (pin "6") (pinfunction "SDA_6") (pintype "passive"))
      (node (ref "U7") (pin "B2") (pinfunction "SDA_B2") (pintype "passive"))
    )
    (net (code "30") (name "GND") (class "Default")
      (node (ref "C1") (pin "1") (pinfunction "1_1") (pintype "passive"))
      (node (ref "C10") (pin "1") (pinfunction "1_1") (pintype "passive"))
      (node (ref "C11") (pin "1") (pinfunction "1_1") (pintype "passive"))
      (node (ref "C12") (pin "1") (pinfunction "1_1") (pintype "passive"))
      (node (ref "C13") (pin "1") (pinfunction "1_1") (pintype "passive"))
      (node (ref "C14") (pin "1") (pinfunction "1_1") (pintype "passive"))
      (node (ref "C15") (pin "1") (pinfunction "1_1") (pintype "passive"))
      (node (ref "C16") (pin "1") (pinfunction "1_1") (pintype "passive"))
      (node (ref "C17") (pin "1") (pinfunction "1_1") (pintype "passive"))
      (node (ref "C18") (pin "1") (pinfunction "1_1") (pintype "passive"))
      (node (ref "C19") (pin "1") (pinfunction "1_1") (pintype "passive"))
      (node (ref "C2") (pin "1") (pinfunction "1_1") (pintype "passive"))
      (node (ref "C20") (pin "1") (pinfunction "1_1") (pintype "passive"))
      (node (ref "C3") (pin "1") (pinfunction "1_1") (pintype "passive"))
      (node (ref "C4") (pin "1") (pinfunction "1_1") (pintype "passive"))
      (node (ref "C5") (pin "1") (pinfunction "1_1") (pintype "passive"))
      (node (ref "C6") (pin "1") (pinfunction "1_1") (pintype "passive"))
      (node (ref "C7") (pin "1") (pinfunction "1_1") (pintype "passive"))
      (node (ref "C8") (pin "1") (pinfunction "1_1") (pintype "passive"))
      (node (ref "C9") (pin "1") (pinfunction "1_1") (pintype "passive"))
      (node (ref "J1") (pin "A1/B12") (pinfunction "GND_A1/B12") (pintype "power_in"))
      (node (ref "J1") (pin "B1/A12") (pinfunction "GND_B1/A12") (pintype "power_in"))
      (node (ref "J1") (pin "SHLD") (pinfunction "SHLD_SHLD") (pintype "power_in"))
      (node (ref "J2") (pin "2") (pinfunction "GND_2") (pintype "passive"))
      (node (ref "Q1") (pin "3") (pinfunction "Source_3") (pintype "passive"))
      (node (ref "R10") (pin "1") (pinfunction "1_1") (pintype "passive"))
      (node (ref "R11") (pin "1") (pinfunction "1_1") (pintype "passive"))
      (node (ref "R13") (pin "1") (pinfunction "1_1") (pintype "passive"))
      (node (ref "R16") (pin "1") (pinfunction "1_1") (pintype "passive"))
      (node (ref "R17") (pin "1") (pinfunction "1_1") (pintype "passive"))
      (node (ref "R18") (pin "1") (pinfunction "1_1") (pintype "passive"))
      (node (ref "R23") (pin "1") (pinfunction "1_1") (pintype "passive"))
      (node (ref "R24") (pin "1") (pinfunction "1_1") (pintype "passive"))
      (node (ref "R3") (pin "1") (pinfunction "1_1") (pintype "passive"))
      (node (ref "R5") (pin "1") (pinfunction "1_1") (pintype "passive"))
      (node (ref "S3") (pin "2") (pintype "passive"))
      (node (ref "S4") (pin "2") (pintype "passive"))
      (node (ref "U1") (pin "1") (pinfunction "GND_1") (pintype "passive"))
      (node (ref "U1") (pin "12") (pinfunction "GND_12") (pintype "passive"))
      (node (ref "U1") (pin "5") (pinfunction "GND_5") (pintype "passive"))
      (node (ref "U1") (pin "6") (pinfunction "GND_6") (pintype "passive"))
      (node (ref "U10") (pin "5") (pinfunction "GND_5") (pintype "passive"))
      (node (ref "U10") (pin "9") (pinfunction "PAD_9") (pintype "passive"))
      (node (ref "U2") (pin "1") (pinfunction "GND_1") (pintype "power_in"))
      (node (ref "U2") (pin "11") (pinfunction "GND_11") (pintype "power_in"))
      (node (ref "U2") (pin "14") (pinfunction "GND_14") (pintype "power_in"))
      (node (ref "U2") (pin "2") (pinfunction "GND_2") (pintype "power_in"))
      (node (ref "U2") (pin "36") (pinfunction "GND_36") (pintype "power_in"))
      (node (ref "U2") (pin "37") (pinfunction "GND_37") (pintype "power_in"))
      (node (ref "U2") (pin "38") (pinfunction "GND_38") (pintype "power_in"))
      (node (ref "U2") (pin "39") (pinfunction "GND_39") (pintype "power_in"))
      (node (ref "U2") (pin "40") (pinfunction "GND_40") (pintype "power_in"))
      (node (ref "U2") (pin "41") (pinfunction "GND_41") (pintype "power_in"))
      (node (ref "U2") (pin "42") (pinfunction "GND_42") (pintype "power_in"))
      (node (ref "U2") (pin "43") (pinfunction "GND_43") (pintype "power_in"))
      (node (ref "U2") (pin "44") (pinfunction "GND_44") (pintype "power_in"))
      (node (ref "U2") (pin "45") (pinfunction "GND_45") (pintype "power_in"))
      (node (ref "U2") (pin "46") (pinfunction "GND_46") (pintype "power_in"))
      (node (ref "U2") (pin "47") (pinfunction "GND_47") (pintype "power_in"))
      (node (ref "U2") (pin "48") (pinfunction "GND_48") (pintype "power_in"))
      (node (ref "U2") (pin "49") (pinfunction "GND_49") (pintype "power_in"))
      (node (ref "U2") (pin "50") (pinfunction "GND_50") (pintype "power_in"))
      (node (ref "U2") (pin "51") (pinfunction "GND_51") (pintype "power_in"))
      (node (ref "U2") (pin "52") (pinfunction "GND_52") (pintype "power_in"))
      (node (ref "U2") (pin "53") (pinfunction "GND_53") (pintype "power_in"))
      (node (ref "U3") (pin "1") (pinfunction "SA0_1") (pintype "bidirectional"))
      (node (ref "U3") (pin "2") (pinfunction "SDx_2") (pintype "passive"))
      (node (ref "U3") (pin "3") (pinfunction "SCx_3") (pintype "passive"))
      (node (ref "U3") (pin "6") (pinfunction "GND_6") (pintype "power_in"))
      (node (ref "U3") (pin "7") (pinfunction "GND_7") (pintype "power_in"))
      (node (ref "U4") (pin "18") (pinfunction "AGND_18") (pintype "power_in"))
      (node (ref "U4") (pin "2") (pinfunction "VD3_2") (pintype "input"))
      (node (ref "U4") (pin "3") (pinfunction "GND_3") (pintype "power_in"))
      (node (ref "U5") (pin "2") (pinfunction "ADDR_2") (pintype "input"))
      (node (ref "U5") (pin "8") (pinfunction "VSS_8") (pintype "power_in"))
      (node (ref "U6") (pin "11") (pinfunction "PAD_11") (pintype "passive"))
      (node (ref "U6") (pin "5") (pinfunction "VSS_5") (pintype "passive"))
      (node (ref "U7") (pin "A1") (pinfunction "VSA_A1") (pintype "passive"))
      (node (ref "U8") (pin "3") (pinfunction "D1_3") (pintype "input"))
      (node (ref "U8") (pin "5") (pinfunction "GND_5") (pintype "power_in"))
      (node (ref "U9") (pin "6") (pinfunction "VSS_6") (pintype "passive"))
      (node (ref "U9") (pin "9") (pinfunction "EPAD_9") (pintype "passive"))
    )
    (net (code "31") (name "Net-(D1-A)") (class "Default")
      (node (ref "D1") (pin "1") (pinfunction "A_1") (pintype "passive"))
      (node (ref "R19") (pin "1") (pinfunction "1_1") (pintype "passive"))
    )
    (net (code "32") (name "Net-(D1-K)") (class "Default")
      (node (ref "D1") (pin "2") (pinfunction "K_2") (pintype "passive"))
      (node (ref "U9") (pin "5") (pinfunction "STAT_5") (pintype "output"))
    )
    (net (code "33") (name "Net-(J1-CC1)") (class "Default")
      (node (ref "J1") (pin "A5") (pinfunction "CC1_A5") (pintype "passive"))
      (node (ref "R11") (pin "2") (pinfunction "2_2") (pintype "passive"))
    )
    (net (code "34") (name "Net-(J1-CC2)") (class "Default")
      (node (ref "J1") (pin "B5") (pinfunction "CC2_B5") (pintype "passive"))
      (node (ref "R10") (pin "2") (pinfunction "2_2") (pintype "passive"))
    )
    (net (code "35") (name "Net-(Q1-Gate)") (class "Default")
      (node (ref "Q1") (pin "2") (pinfunction "Gate_2") (pintype "passive"))
      (node (ref "R1") (pin "1") (pinfunction "1_1") (pintype "passive"))
      (node (ref "R3") (pin "2") (pinfunction "2_2") (pintype "passive"))
    )
    (net (code "36") (name "Net-(Q2-Source)") (class "Default")
      (node (ref "C12") (pin "2") (pinfunction "2_2") (pintype "passive"))
      (node (ref "Q2") (pin "3") (pinfunction "Source_3") (pintype "passive"))
      (node (ref "U7") (pin "B1") (pinfunction "VDD_B1") (pintype "passive"))
    )
    (net (code "37") (name "Net-(U1-LED_A)") (class "Default")
      (node (ref "R2") (pin "1") (pinfunction "1_1") (pintype "passive"))
      (node (ref "U1") (pin "3") (pinfunction "LED_A_3") (pintype "passive"))
    )
    (net (code "38") (name "Net-(U4-SIGREF)") (class "Default")
      (node (ref "C9") (pin "2") (pinfunction "2_2") (pintype "passive"))
      (node (ref "U4") (pin "20") (pinfunction "SIGREF_20") (pintype "output"))
    )
    (net (code "39") (name "Net-(U4-SIGREF_ECG)") (class "Default")
      (node (ref "C8") (pin "2") (pinfunction "2_2") (pintype "passive"))
      (node (ref "U4") (pin "19") (pinfunction "SIGREF_ECG_19") (pintype "output"))
    )
    (net (code "40") (name "Net-(U4-V_LDO)") (class "Default")
      (node (ref "C7") (pin "2") (pinfunction "2_2") (pintype "passive"))
      (node (ref "U4") (pin "17") (pinfunction "V_LDO_17") (pintype "output"))
    )
    (net (code "41") (name "Net-(U6-CLKOE)") (class "Default")
      (node (ref "R13") (pin "2") (pinfunction "2_2") (pintype "passive"))
      (node (ref "U6") (pin "3") (pinfunction "CLKOE_3") (pintype "passive"))
    )
    (net (code "42") (name "Net-(U6-OSCI)") (class "Default")
      (node (ref "U6") (pin "1") (pinfunction "OSCI_1") (pintype "passive"))
      (node (ref "Y1") (pin "1") (pinfunction "In/Out_1") (pintype "passive"))
    )
    (net (code "43") (name "Net-(U6-OSCO)") (class "Default")
      (node (ref "U6") (pin "2") (pinfunction "OSCO_2") (pintype "passive"))
      (node (ref "Y1") (pin "2") (pinfunction "Out/In_2") (pintype "passive"))
    )
    (net (code "44") (name "Net-(U8-ILIM)") (class "Default")
      (node (ref "R23") (pin "2") (pinfunction "2_2") (pintype "passive"))
      (node (ref "U8") (pin "4") (pinfunction "ILIM_4") (pintype "input"))
    )
    (net (code "45") (name "Net-(U9-PROG)") (class "Default")
      (node (ref "R24") (pin "2") (pinfunction "2_2") (pintype "passive"))
      (node (ref "U9") (pin "8") (pinfunction "PROG_8") (pintype "input"))
    )
    (net (code "46") (name "Net-(U10-CE)") (class "Default")
      (node (ref "R21") (pin "1") (pinfunction "1_1") (pintype "passive"))
      (node (ref "U10") (pin "6") (pinfunction "CE_6") (pintype "passive"))
    )
    (net (code "47") (name "Net-(U10-LCON)") (class "Default")
      (node (ref "R22") (pin "1") (pinfunction "1_1") (pintype "passive"))
      (node (ref "U10") (pin "3") (pinfunction "LCON_3") (pintype "passive"))
    )
    (net (code "48") (name "unconnected-(J1-SBU1-PadA8)") (class "Default")
      (node (ref "J1") (pin "A8") (pinfunction "SBU1_A8") (pintype "passive+no_connect"))
    )
    (net (code "49") (name "unconnected-(J1-SBU2-PadB8)") (class "Default")
      (node (ref "J1") (pin "B8") (pinfunction "SBU2_B8") (pintype "passive+no_connect"))
    )
    (net (code "50") (name "unconnected-(U2-NC-Pad4)") (class "Default")
      (node (ref "U2") (pin "4") (pinfunction "NC_4") (pintype "passive+no_connect"))
    )
    (net (code "51") (name "unconnected-(U2-NC-Pad7)") (class "Default")
      (node (ref "U2") (pin "7") (pinfunction "NC_7") (pintype "passive+no_connect"))
    )
    (net (code "52") (name "unconnected-(U2-NC-Pad9)") (class "Default")
      (node (ref "U2") (pin "9") (pinfunction "NC_9") (pintype "passive+no_connect"))
    )
    (net (code "53") (name "unconnected-(U2-NC-Pad10)") (class "Default")
      (node (ref "U2") (pin "10") (pinfunction "NC_10") (pintype "passive+no_connect"))
    )
    (net (code "54") (name "unconnected-(U2-NC-Pad15)") (class "Default")
      (node (ref "U2") (pin "15") (pinfunction "NC_15") (pintype "passive+no_connect"))
    )
    (net (code "55") (name "unconnected-(U2-NC-Pad17)") (class "Default")
      (node (ref "U2") (pin "17") (pinfunction "NC_17") (pintype "passive+no_connect"))
    )
    (net (code "56") (name "unconnected-(U2-NC-Pad24)") (class "Default")
      (node (ref "U2") (pin "24") (pinfunction "NC_24") (pintype "passive+no_connect"))
    )
    (net (code "57") (name "unconnected-(U2-NC-Pad25)") (class "Default")
      (node (ref "U2") (pin "25") (pinfunction "NC_25") (pintype "passive+no_connect"))
    )
    (net (code "58") (name "unconnected-(U2-NC-Pad28)") (class "Default")
      (node (ref "U2") (pin "28") (pinfunction "NC_28") (pintype "passive+no_connect"))
    )
    (net (code "59") (name "unconnected-(U2-NC-Pad29)") (class "Default")
      (node (ref "U2") (pin "29") (pinfunction "NC_29") (pintype "passive+no_connect"))
    )
    (net (code "60") (name "unconnected-(U2-NC-Pad32)") (class "Default")
      (node (ref "U2") (pin "32") (pinfunction "NC_32") (pintype "passive+no_connect"))
    )
    (net (code "61") (name "unconnected-(U2-NC-Pad33)") (class "Default")
      (node (ref "U2") (pin "33") (pinfunction "NC_33") (pintype "passive+no_connect"))
    )
    (net (code "62") (name "unconnected-(U2-NC-Pad34)") (class "Default")
      (node (ref "U2") (pin "34") (pinfunction "NC_34") (pintype "passive+no_connect"))
    )
    (net (code "63") (name "unconnected-(U2-NC-Pad35)") (class "Default")
      (node (ref "U2") (pin "35") (pinfunction "NC_35") (pintype "passive+no_connect"))
    )
    (net (code "64") (name "unconnected-(U3-INT2-Pad9)") (class "Default")
      (node (ref "U3") (pin "9") (pinfunction "INT2_9") (pintype "bidirectional+no_connect"))
    )
    (net (code "65") (name "unconnected-(U3-NC-Pad10)") (class "Default")
      (node (ref "U3") (pin "10") (pinfunction "NC_10") (pintype "passive+no_connect"))
    )
    (net (code "66") (name "unconnected-(U3-NC-Pad11)") (class "Default")
      (node (ref "U3") (pin "11") (pinfunction "NC_11") (pintype "passive+no_connect"))
    )
    (net (code "67") (name "unconnected-(U4-ECG_INN-Pad5)") (class "Default")
      (node (ref "U4") (pin "5") (pinfunction "ECG_INN_5") (pintype "input+no_connect"))
    )
    (net (code "68") (name "unconnected-(U4-ECG_INP-Pad4)") (class "Default")
      (node (ref "U4") (pin "4") (pinfunction "ECG_INP_4") (pintype "input+no_connect"))
    )
    (net (code "69") (name "unconnected-(U4-ECG_REF-Pad6)") (class "Default")
      (node (ref "U4") (pin "6") (pinfunction "ECG_REF_6") (pintype "output+no_connect"))
    )
    (net (code "70") (name "unconnected-(U4-GPIO0-Pad13)") (class "Default")
      (node (ref "U4") (pin "13") (pinfunction "GPIO0_13") (pintype "bidirectional+no_connect"))
    )
    (net (code "71") (name "unconnected-(U4-GPIO1-Pad14)") (class "Default")
      (node (ref "U4") (pin "14") (pinfunction "GPIO1_14") (pintype "bidirectional+no_connect"))
    )
    (net (code "72") (name "unconnected-(U4-GPIO2-Pad15)") (class "Default")
      (node (ref "U4") (pin "15") (pinfunction "GPIO2_15") (pintype "bidirectional+no_connect"))
    )
    (net (code "73") (name "unconnected-(U4-GPIO3-Pad16)") (class "Default")
      (node (ref "U4") (pin "16") (pinfunction "GPIO3_16") (pintype "bidirectional+no_connect"))
    )
    (net (code "74") (name "unconnected-(U4-NC-Pad11)") (class "Default")
      (node (ref "U4") (pin "11") (pinfunction "NC_11") (pintype "passive+no_connect"))
    )
    (net (code "75") (name "unconnected-(U5-P7-Pad12)") (class "Default")
      (node (ref "U5") (pin "12") (pinfunction "P7_12") (pintype "bidirectional+no_connect"))
    )
    (net (code "76") (name "unconnected-(U6-CLKOUT-Pad9)") (class "Default")
      (node (ref "U6") (pin "9") (pinfunction "CLKOUT_9") (pintype "passive+no_connect"))
    )
    (net (code "77") (name "unconnected-(U6-NC-Pad8)") (class "Default")
      (node (ref "U6") (pin "8") (pinfunction "NC_8") (pintype "passive+no_connect"))
    )
    (net (code "78") (name "unconnected-(U9-NC-Pad7)") (class "Default")
      (node (ref "U9") (pin "7") (pinfunction "NC_7") (pintype "passive+no_connect"))
    )
  )
)
